# Analog.net
KiCad netlist of a schematic drawn in Altium Designer
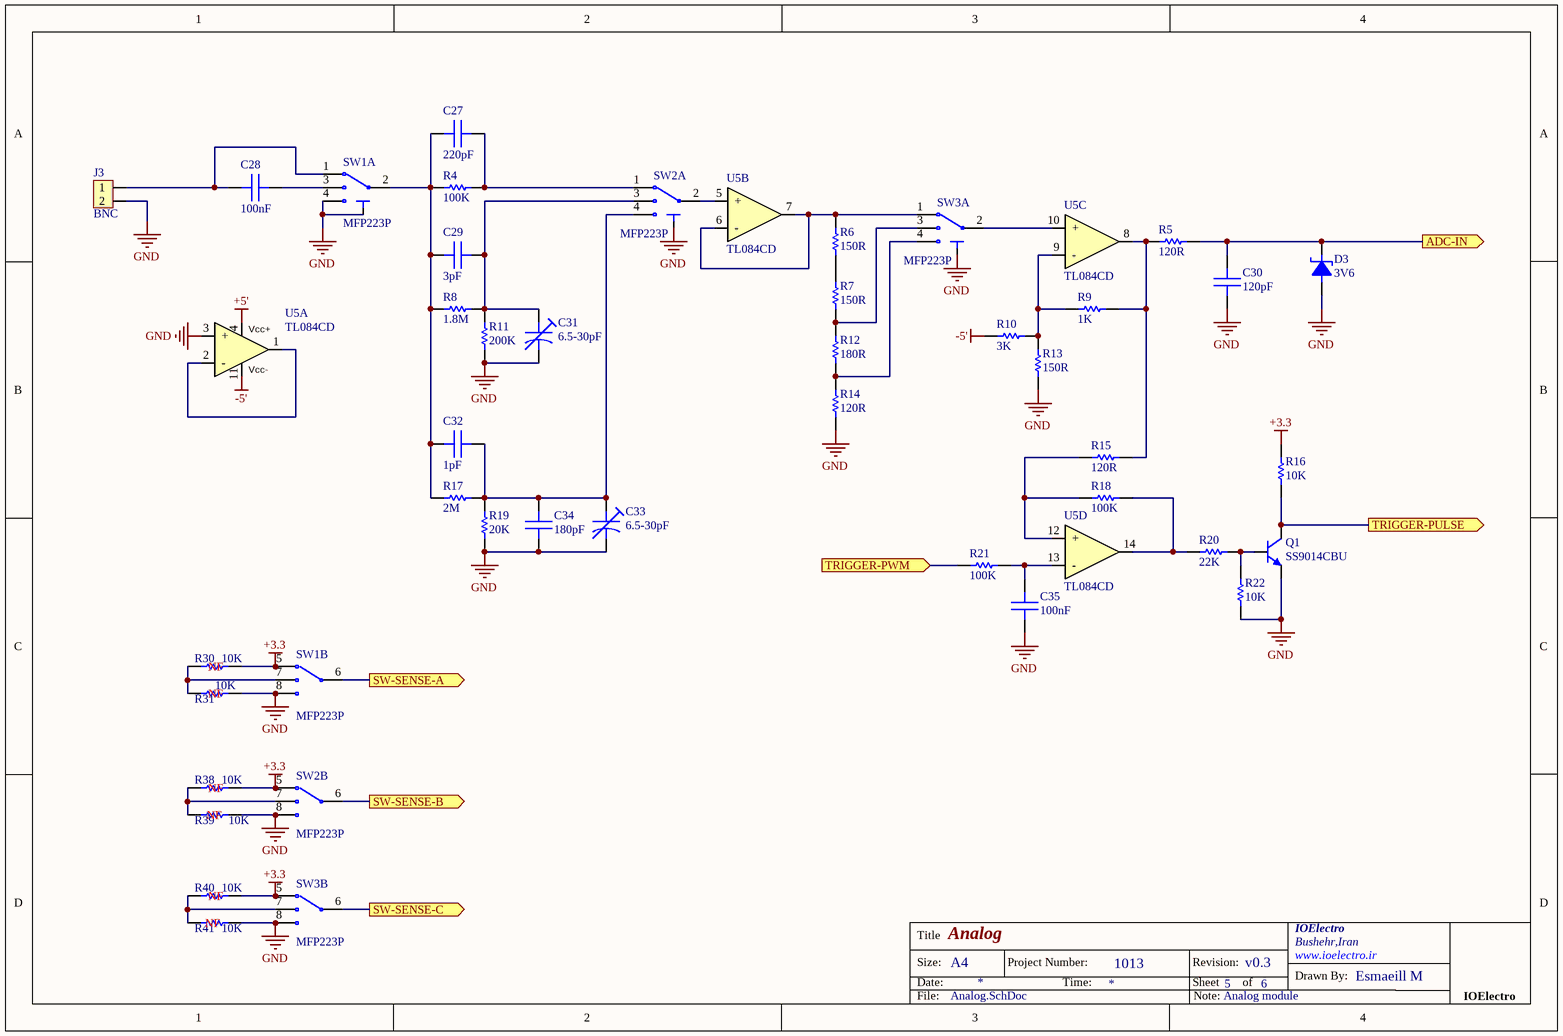
[diagram p0: Analog.SchDoc]

(export (version "E")
  (design (tool "Eeschema 10.0.6"))
  (components
    (comp (ref "C27")
      (value "220pF")
      (footprint "C-BP-Ceramic-DIP")
      (description "Ceramic Disk Capacitor 50V")
      (libsource (lib "IOElectro") (part "CAP"))
    )
    (comp (ref "C28")
      (value "100nF")
      (footprint "C-BP-Ceramic-DIP")
      (description "Ceramic Disk Capacitor 50V")
      (libsource (lib "IOElectro") (part "CAP"))
    )
    (comp (ref "C29")
      (value "3pF")
      (footprint "C-BP-Ceramic-DIP")
      (description "Ceramic Disk Capacitor 50V")
      (libsource (lib "IOElectro") (part "CAP"))
    )
    (comp (ref "C30")
      (value "120pF")
      (footprint "C-BP-Ceramic-DIP")
      (description "Ceramic Disk Capacitor 50V")
      (libsource (lib "IOElectro") (part "CAP"))
    )
    (comp (ref "C31")
      (value "6.5-30pF")
      (footprint "C-TR-DIP_5mm")
      (description "Trimmer / Variable Capacitors 6.5-30pF 100V 85 DEG")
      (fields
        (field (name "MANUFACTURER") "Sprague Goodman")
        (field (name "MANUFACTURER PART NUMBER") "GKG30015")
      )
      (libsource (lib "IOElectro") (part "GKG30015"))
    )
    (comp (ref "C32")
      (value "1pF")
      (footprint "C-BP-Ceramic-DIP")
      (description "Ceramic Disk Capacitor 50V")
      (libsource (lib "IOElectro") (part "CAP"))
    )
    (comp (ref "C33")
      (value "6.5-30pF")
      (footprint "C-TR-DIP_5mm")
      (description "Trimmer / Variable Capacitors 6.5-30pF 100V 85 DEG")
      (fields
        (field (name "MANUFACTURER") "Sprague Goodman")
        (field (name "MANUFACTURER PART NUMBER") "GKG30015")
      )
      (libsource (lib "IOElectro") (part "GKG30015"))
    )
    (comp (ref "C34")
      (value "180pF")
      (footprint "C-BP-Ceramic-DIP")
      (description "Ceramic Disk Capacitor 50V")
      (libsource (lib "IOElectro") (part "CAP"))
    )
    (comp (ref "C35")
      (value "100nF")
      (footprint "C-BP-Ceramic-DIP")
      (description "Ceramic Disk Capacitor 50V")
      (libsource (lib "IOElectro") (part "CAP"))
    )
    (comp (ref "D3")
      (value "3V6")
      (footprint "SOD80")
      (description "SMD MiniMELF")
      (libsource (lib "IOElectro") (part "DIODE-Z"))
    )
    (comp (ref "J3")
      (value "BNC")
      (footprint "PH-1X2-N3D")
      (description "PIN HEADER 1x2 2.56mm")
      (libsource (lib "Schlib") (part "PH-1X2"))
    )
    (comp (ref "Q1")
      (value "SS9014CBU")
      (footprint "TO-92")
      (description "Bipolar (BJT) Single Transistor, NPN, 45 V, 270 MHz, 450 mW, 100 mA, 200")
      (fields (field (name "MANUFACTURER") "ON Semiconductor"))
      (libsource (lib "IOElectro") (part "SS9014CBU"))
    )
    (comp (ref "R4")
      (value "100K")
      (footprint "R-1/4W-DIP-Blue")
      (description "Resistor DIP 1/4W 1%")
      (libsource (lib "IOElectro") (part "RES"))
    )
    (comp (ref "R5")
      (value "120R")
      (footprint "R-1/4W-DIP-Blue")
      (description "Resistor DIP 1/4W 1%")
      (libsource (lib "IOElectro") (part "RES"))
    )
    (comp (ref "R6")
      (value "150R")
      (footprint "R-1/4W-DIP-Blue")
      (description "Resistor DIP 1/4W 1%")
      (libsource (lib "IOElectro") (part "RES"))
    )
    (comp (ref "R7")
      (value "150R")
      (footprint "R-1/4W-DIP-Blue")
      (description "Resistor DIP 1/4W 1%")
      (libsource (lib "IOElectro") (part "RES"))
    )
    (comp (ref "R8")
      (value "1.8M")
      (footprint "R-1/4W-DIP-Blue")
      (description "Resistor DIP 1/4W 1%")
      (libsource (lib "IOElectro") (part "RES"))
    )
    (comp (ref "R9")
      (value "1K")
      (footprint "R-1/4W-DIP-Blue")
      (description "Resistor DIP 1/4W 1%")
      (libsource (lib "IOElectro") (part "RES"))
    )
    (comp (ref "R10")
      (value "3K")
      (footprint "R-1/4W-DIP-Blue")
      (description "Resistor DIP 1/4W 1%")
      (libsource (lib "IOElectro") (part "RES"))
    )
    (comp (ref "R11")
      (value "200K")
      (footprint "R-1/4W-DIP-Blue")
      (description "Resistor DIP 1/4W 1%")
      (libsource (lib "IOElectro") (part "RES"))
    )
    (comp (ref "R12")
      (value "180R")
      (footprint "R-1/4W-DIP-Blue")
      (description "Resistor DIP 1/4W 1%")
      (libsource (lib "IOElectro") (part "RES"))
    )
    (comp (ref "R13")
      (value "150R")
      (footprint "R-1/4W-DIP-Blue")
      (description "Resistor DIP 1/4W 1%")
      (libsource (lib "IOElectro") (part "RES"))
    )
    (comp (ref "R14")
      (value "120R")
      (footprint "R-1/4W-DIP-Blue")
      (description "Resistor DIP 1/4W 1%")
      (libsource (lib "IOElectro") (part "RES"))
    )
    (comp (ref "R15")
      (value "120R")
      (footprint "R-1/4W-DIP-Blue")
      (description "Resistor DIP 1/4W 1%")
      (libsource (lib "IOElectro") (part "RES"))
    )
    (comp (ref "R16")
      (value "10K")
      (footprint "R-0805")
      (description "0805")
      (libsource (lib "IOElectro") (part "RES"))
    )
    (comp (ref "R17")
      (value "2M")
      (footprint "R-1/4W-DIP-Blue")
      (description "Resistor DIP 1/4W 1%")
      (libsource (lib "IOElectro") (part "RES"))
    )
    (comp (ref "R18")
      (value "100K")
      (footprint "R-1/4W-DIP-Blue")
      (description "Resistor DIP 1/4W 1%")
      (libsource (lib "IOElectro") (part "RES"))
    )
    (comp (ref "R19")
      (value "20K")
      (footprint "R-1/4W-DIP-Blue")
      (description "Resistor DIP 1/4W 1%")
      (libsource (lib "IOElectro") (part "RES"))
    )
    (comp (ref "R20")
      (value "22K")
      (footprint "R-0805")
      (description "0805")
      (libsource (lib "IOElectro") (part "RES"))
    )
    (comp (ref "R21")
      (value "100K")
      (footprint "R-1/4W-DIP-Blue")
      (description "Resistor DIP 1/4W 1%")
      (libsource (lib "IOElectro") (part "RES"))
    )
    (comp (ref "R22")
      (value "10K")
      (footprint "R-0805")
      (description "0805")
      (libsource (lib "IOElectro") (part "RES"))
    )
    (comp (ref "R30")
      (value "10K")
      (footprint "R-0805")
      (description "0805")
      (libsource (lib "IOElectro") (part "RES"))
    )
    (comp (ref "R31")
      (value "10K")
      (footprint "R-0805")
      (description "0805")
      (libsource (lib "IOElectro") (part "RES"))
    )
    (comp (ref "R38")
      (value "10K")
      (footprint "R-0805")
      (description "0805")
      (libsource (lib "IOElectro") (part "RES"))
    )
    (comp (ref "R39")
      (value "10K")
      (footprint "R-0805")
      (description "0805")
      (libsource (lib "IOElectro") (part "RES"))
    )
    (comp (ref "R40")
      (value "10K")
      (footprint "R-0805")
      (description "0805")
      (libsource (lib "IOElectro") (part "RES"))
    )
    (comp (ref "R41")
      (value "10K")
      (footprint "R-0805")
      (description "0805")
      (libsource (lib "IOElectro") (part "RES"))
    )
    (comp (ref "SW1")
      (value "MFP223P")
      (footprint "MFP223P")
      (description "Switch Slide ON ON ON Extended Top Slide 0.35A 30VDC 10000Cycle PC Pins Bracket Mount/Through Hole")
      (fields (field (name "MANUFACTURER") "Knitter-Switch"))
      (libsource (lib "Schlib") (part "MFP223P"))
    )
    (comp (ref "SW2")
      (value "MFP223P")
      (footprint "MFP223P")
      (description "Switch Slide ON ON ON Extended Top Slide 0.35A 30VDC 10000Cycle PC Pins Bracket Mount/Through Hole")
      (fields (field (name "MANUFACTURER") "Knitter-Switch"))
      (libsource (lib "IOElectro") (part "MFP223P"))
    )
    (comp (ref "SW3")
      (value "MFP223P")
      (footprint "MFP223P")
      (description "Switch Slide ON ON ON Extended Top Slide 0.35A 30VDC 10000Cycle PC Pins Bracket Mount/Through Hole")
      (fields (field (name "MANUFACTURER") "Knitter-Switch"))
      (libsource (lib "IOElectro") (part "MFP223P"))
    )
    (comp (ref "U5")
      (value "TL084CD")
      (footprint "SO-14")
      (description "IC OPAMP JFET 4MHZ 14SO")
      (fields (field (name "MANUFACTURER") "STMicroelectronics"))
      (libsource (lib "IOElectro") (part "TL084CD"))
    )
  )
  (nets
    (net (code "1") (name "+3.3") (class "Default")
      (node (ref "R16") (pin "2") (pinfunction "2_2") (pintype "passive"))
      (node (ref "R30") (pin "1") (pinfunction "1_1") (pintype "passive"))
      (node (ref "R38") (pin "1") (pinfunction "1_1") (pintype "passive"))
      (node (ref "R40") (pin "1") (pinfunction "1_1") (pintype "passive"))
      (node (ref "SW1") (pin "5") (pinfunction "5_5") (pintype "passive"))
      (node (ref "SW2") (pin "5") (pinfunction "5_5") (pintype "passive"))
      (node (ref "SW3") (pin "5") (pinfunction "5_5") (pintype "passive"))
    )
    (net (code "2") (name "+5'") (class "Default")
      (node (ref "U5") (pin "4") (pinfunction "Vcc+_4") (pintype "passive"))
    )
    (net (code "3") (name "-5'") (class "Default")
      (node (ref "R10") (pin "1") (pinfunction "1_1") (pintype "passive"))
      (node (ref "U5") (pin "11") (pinfunction "Vcc-_11") (pintype "passive"))
    )
    (net (code "4") (name "/ADC-IN") (class "Default")
      (node (ref "C30") (pin "1") (pinfunction "1_1") (pintype "passive"))
      (node (ref "D3") (pin "K") (pinfunction "K_K") (pintype "passive"))
      (node (ref "R5") (pin "1") (pinfunction "1_1") (pintype "passive"))
    )
    (net (code "5") (name "/SW-SENSE-A") (class "Default")
      (node (ref "SW1") (pin "6") (pinfunction "6_6") (pintype "passive"))
    )
    (net (code "6") (name "/SW-SENSE-B") (class "Default")
      (node (ref "SW2") (pin "6") (pinfunction "6_6") (pintype "passive"))
    )
    (net (code "7") (name "/SW-SENSE-C") (class "Default")
      (node (ref "SW3") (pin "6") (pinfunction "6_6") (pintype "passive"))
    )
    (net (code "8") (name "/TRIGGER-PULSE") (class "Default")
      (node (ref "Q1") (pin "3") (pinfunction "C_3") (pintype "passive"))
      (node (ref "R16") (pin "1") (pinfunction "1_1") (pintype "passive"))
    )
    (net (code "9") (name "/TRIGGER-PWM") (class "Default")
      (node (ref "R21") (pin "2") (pinfunction "2_2") (pintype "passive"))
    )
    (net (code "10") (name "GND") (class "Default")
      (node (ref "C30") (pin "2") (pinfunction "2_2") (pintype "passive"))
      (node (ref "C31") (pin "K") (pinfunction "K_K") (pintype "passive"))
      (node (ref "C33") (pin "K") (pinfunction "K_K") (pintype "passive"))
      (node (ref "C34") (pin "2") (pinfunction "2_2") (pintype "passive"))
      (node (ref "C35") (pin "2") (pinfunction "2_2") (pintype "passive"))
      (node (ref "D3") (pin "A") (pinfunction "A_A") (pintype "passive"))
      (node (ref "J3") (pin "2") (pinfunction "2_2") (pintype "passive"))
      (node (ref "Q1") (pin "1") (pinfunction "E_1") (pintype "passive"))
      (node (ref "R11") (pin "1") (pinfunction "1_1") (pintype "passive"))
      (node (ref "R13") (pin "2") (pinfunction "2_2") (pintype "passive"))
      (node (ref "R14") (pin "1") (pinfunction "1_1") (pintype "passive"))
      (node (ref "R19") (pin "1") (pinfunction "1_1") (pintype "passive"))
      (node (ref "R22") (pin "1") (pinfunction "1_1") (pintype "passive"))
      (node (ref "R31") (pin "1") (pinfunction "1_1") (pintype "passive"))
      (node (ref "R39") (pin "1") (pinfunction "1_1") (pintype "passive"))
      (node (ref "R41") (pin "1") (pinfunction "1_1") (pintype "passive"))
      (node (ref "SW1") (pin "0") (pinfunction "0_0") (pintype "passive"))
      (node (ref "SW1") (pin "4") (pinfunction "4_4") (pintype "passive"))
      (node (ref "SW1") (pin "8") (pinfunction "5_8") (pintype "passive"))
      (node (ref "SW2") (pin "0") (pinfunction "0_0") (pintype "passive"))
      (node (ref "SW2") (pin "8") (pinfunction "5_8") (pintype "passive"))
      (node (ref "SW3") (pin "0") (pinfunction "0_0") (pintype "passive"))
      (node (ref "SW3") (pin "8") (pinfunction "5_8") (pintype "passive"))
      (node (ref "U5") (pin "3") (pinfunction "+_3") (pintype "passive"))
    )
    (net (code "11") (name "Net-(C27-Pad1)") (class "Default")
      (node (ref "C27") (pin "1") (pinfunction "1_1") (pintype "passive"))
      (node (ref "R4") (pin "2") (pinfunction "2_2") (pintype "passive"))
      (node (ref "SW2") (pin "1") (pinfunction "1_1") (pintype "passive"))
    )
    (net (code "12") (name "Net-(C27-Pad2)") (class "Default")
      (node (ref "C27") (pin "2") (pinfunction "2_2") (pintype "passive"))
      (node (ref "C29") (pin "2") (pinfunction "2_2") (pintype "passive"))
      (node (ref "C32") (pin "2") (pinfunction "2_2") (pintype "passive"))
      (node (ref "R17") (pin "1") (pinfunction "1_1") (pintype "passive"))
      (node (ref "R4") (pin "1") (pinfunction "1_1") (pintype "passive"))
      (node (ref "R8") (pin "1") (pinfunction "1_1") (pintype "passive"))
      (node (ref "SW1") (pin "2") (pinfunction "2_2") (pintype "passive"))
    )
    (net (code "13") (name "Net-(C28-Pad1)") (class "Default")
      (node (ref "C28") (pin "1") (pinfunction "1_1") (pintype "passive"))
      (node (ref "SW1") (pin "3") (pinfunction "3_3") (pintype "passive"))
    )
    (net (code "14") (name "Net-(C28-Pad2)") (class "Default")
      (node (ref "C28") (pin "2") (pinfunction "2_2") (pintype "passive"))
      (node (ref "J3") (pin "1") (pinfunction "1_1") (pintype "passive"))
      (node (ref "SW1") (pin "1") (pinfunction "1_1") (pintype "passive"))
    )
    (net (code "15") (name "Net-(C29-Pad1)") (class "Default")
      (node (ref "C29") (pin "1") (pinfunction "1_1") (pintype "passive"))
      (node (ref "C31") (pin "A") (pinfunction "A_A") (pintype "passive"))
      (node (ref "R11") (pin "2") (pinfunction "2_2") (pintype "passive"))
      (node (ref "R8") (pin "2") (pinfunction "2_2") (pintype "passive"))
      (node (ref "SW2") (pin "3") (pinfunction "3_3") (pintype "passive"))
    )
    (net (code "16") (name "Net-(C32-Pad1)") (class "Default")
      (node (ref "C32") (pin "1") (pinfunction "1_1") (pintype "passive"))
      (node (ref "C33") (pin "A") (pinfunction "A_A") (pintype "passive"))
      (node (ref "C34") (pin "1") (pinfunction "1_1") (pintype "passive"))
      (node (ref "R17") (pin "2") (pinfunction "2_2") (pintype "passive"))
      (node (ref "R19") (pin "2") (pinfunction "2_2") (pintype "passive"))
      (node (ref "SW2") (pin "4") (pinfunction "4_4") (pintype "passive"))
    )
    (net (code "17") (name "Net-(Q1-B)") (class "Default")
      (node (ref "Q1") (pin "2") (pinfunction "B_2") (pintype "passive"))
      (node (ref "R20") (pin "1") (pinfunction "1_1") (pintype "passive"))
      (node (ref "R22") (pin "2") (pinfunction "2_2") (pintype "passive"))
    )
    (net (code "18") (name "Net-(R6-Pad1)") (class "Default")
      (node (ref "R6") (pin "1") (pinfunction "1_1") (pintype "passive"))
      (node (ref "R7") (pin "2") (pinfunction "2_2") (pintype "passive"))
    )
    (net (code "19") (name "Net-(R12-Pad1)") (class "Default")
      (node (ref "R12") (pin "1") (pinfunction "1_1") (pintype "passive"))
      (node (ref "R14") (pin "2") (pinfunction "2_2") (pintype "passive"))
      (node (ref "SW3") (pin "4") (pinfunction "4_4") (pintype "passive"))
    )
    (net (code "20") (name "Net-(R12-Pad2)") (class "Default")
      (node (ref "R12") (pin "2") (pinfunction "2_2") (pintype "passive"))
      (node (ref "R7") (pin "1") (pinfunction "1_1") (pintype "passive"))
      (node (ref "SW3") (pin "3") (pinfunction "3_3") (pintype "passive"))
    )
    (net (code "21") (name "Net-(R30-Pad2)") (class "Default")
      (node (ref "R30") (pin "2") (pinfunction "2_2") (pintype "passive"))
      (node (ref "R31") (pin "2") (pinfunction "2_2") (pintype "passive"))
      (node (ref "SW1") (pin "7") (pinfunction "7_7") (pintype "passive"))
    )
    (net (code "22") (name "Net-(R38-Pad2)") (class "Default")
      (node (ref "R38") (pin "2") (pinfunction "2_2") (pintype "passive"))
      (node (ref "R39") (pin "2") (pinfunction "2_2") (pintype "passive"))
      (node (ref "SW2") (pin "7") (pinfunction "7_7") (pintype "passive"))
    )
    (net (code "23") (name "Net-(R40-Pad2)") (class "Default")
      (node (ref "R40") (pin "2") (pinfunction "2_2") (pintype "passive"))
      (node (ref "R41") (pin "2") (pinfunction "2_2") (pintype "passive"))
      (node (ref "SW3") (pin "7") (pinfunction "7_7") (pintype "passive"))
    )
    (net (code "24") (name "Net-(U5A--)") (class "Default")
      (node (ref "U5") (pin "1") (pinfunction "O_1") (pintype "passive"))
      (node (ref "U5") (pin "2") (pinfunction "-_2") (pintype "passive"))
    )
    (net (code "25") (name "Net-(U5B-+)") (class "Default")
      (node (ref "SW2") (pin "2") (pinfunction "2_2") (pintype "passive"))
      (node (ref "U5") (pin "5") (pinfunction "+_5") (pintype "passive"))
    )
    (net (code "26") (name "Net-(U5B--)") (class "Default")
      (node (ref "R6") (pin "2") (pinfunction "2_2") (pintype "passive"))
      (node (ref "SW3") (pin "1") (pinfunction "1_1") (pintype "passive"))
      (node (ref "U5") (pin "6") (pinfunction "-_6") (pintype "passive"))
      (node (ref "U5") (pin "7") (pinfunction "O_7") (pintype "passive"))
    )
    (net (code "27") (name "Net-(U5C-+)") (class "Default")
      (node (ref "SW3") (pin "2") (pinfunction "2_2") (pintype "passive"))
      (node (ref "U5") (pin "10") (pinfunction "+_10") (pintype "passive"))
    )
    (net (code "28") (name "Net-(U5C--)") (class "Default")
      (node (ref "R10") (pin "2") (pinfunction "2_2") (pintype "passive"))
      (node (ref "R13") (pin "1") (pinfunction "1_1") (pintype "passive"))
      (node (ref "R9") (pin "2") (pinfunction "2_2") (pintype "passive"))
      (node (ref "U5") (pin "9") (pinfunction "-_9") (pintype "passive"))
    )
    (net (code "29") (name "Net-(U5C-O)") (class "Default")
      (node (ref "R15") (pin "1") (pinfunction "1_1") (pintype "passive"))
      (node (ref "R5") (pin "2") (pinfunction "2_2") (pintype "passive"))
      (node (ref "R9") (pin "1") (pinfunction "1_1") (pintype "passive"))
      (node (ref "U5") (pin "8") (pinfunction "O_8") (pintype "passive"))
    )
    (net (code "30") (name "Net-(U5D-+)") (class "Default")
      (node (ref "R15") (pin "2") (pinfunction "2_2") (pintype "passive"))
      (node (ref "R18") (pin "2") (pinfunction "2_2") (pintype "passive"))
      (node (ref "U5") (pin "12") (pinfunction "+_12") (pintype "passive"))
    )
    (net (code "31") (name "Net-(U5D--)") (class "Default")
      (node (ref "C35") (pin "1") (pinfunction "1_1") (pintype "passive"))
      (node (ref "R21") (pin "1") (pinfunction "1_1") (pintype "passive"))
      (node (ref "U5") (pin "13") (pinfunction "-_13") (pintype "passive"))
    )
    (net (code "32") (name "Net-(U5D-O)") (class "Default")
      (node (ref "R18") (pin "1") (pinfunction "1_1") (pintype "passive"))
      (node (ref "R20") (pin "2") (pinfunction "2_2") (pintype "passive"))
      (node (ref "U5") (pin "14") (pinfunction "O_14") (pintype "passive"))
    )
  )
)
